# STAC_Test_Board_v1_Power.net
KiCad netlist of a schematic drawn in Altium Designer
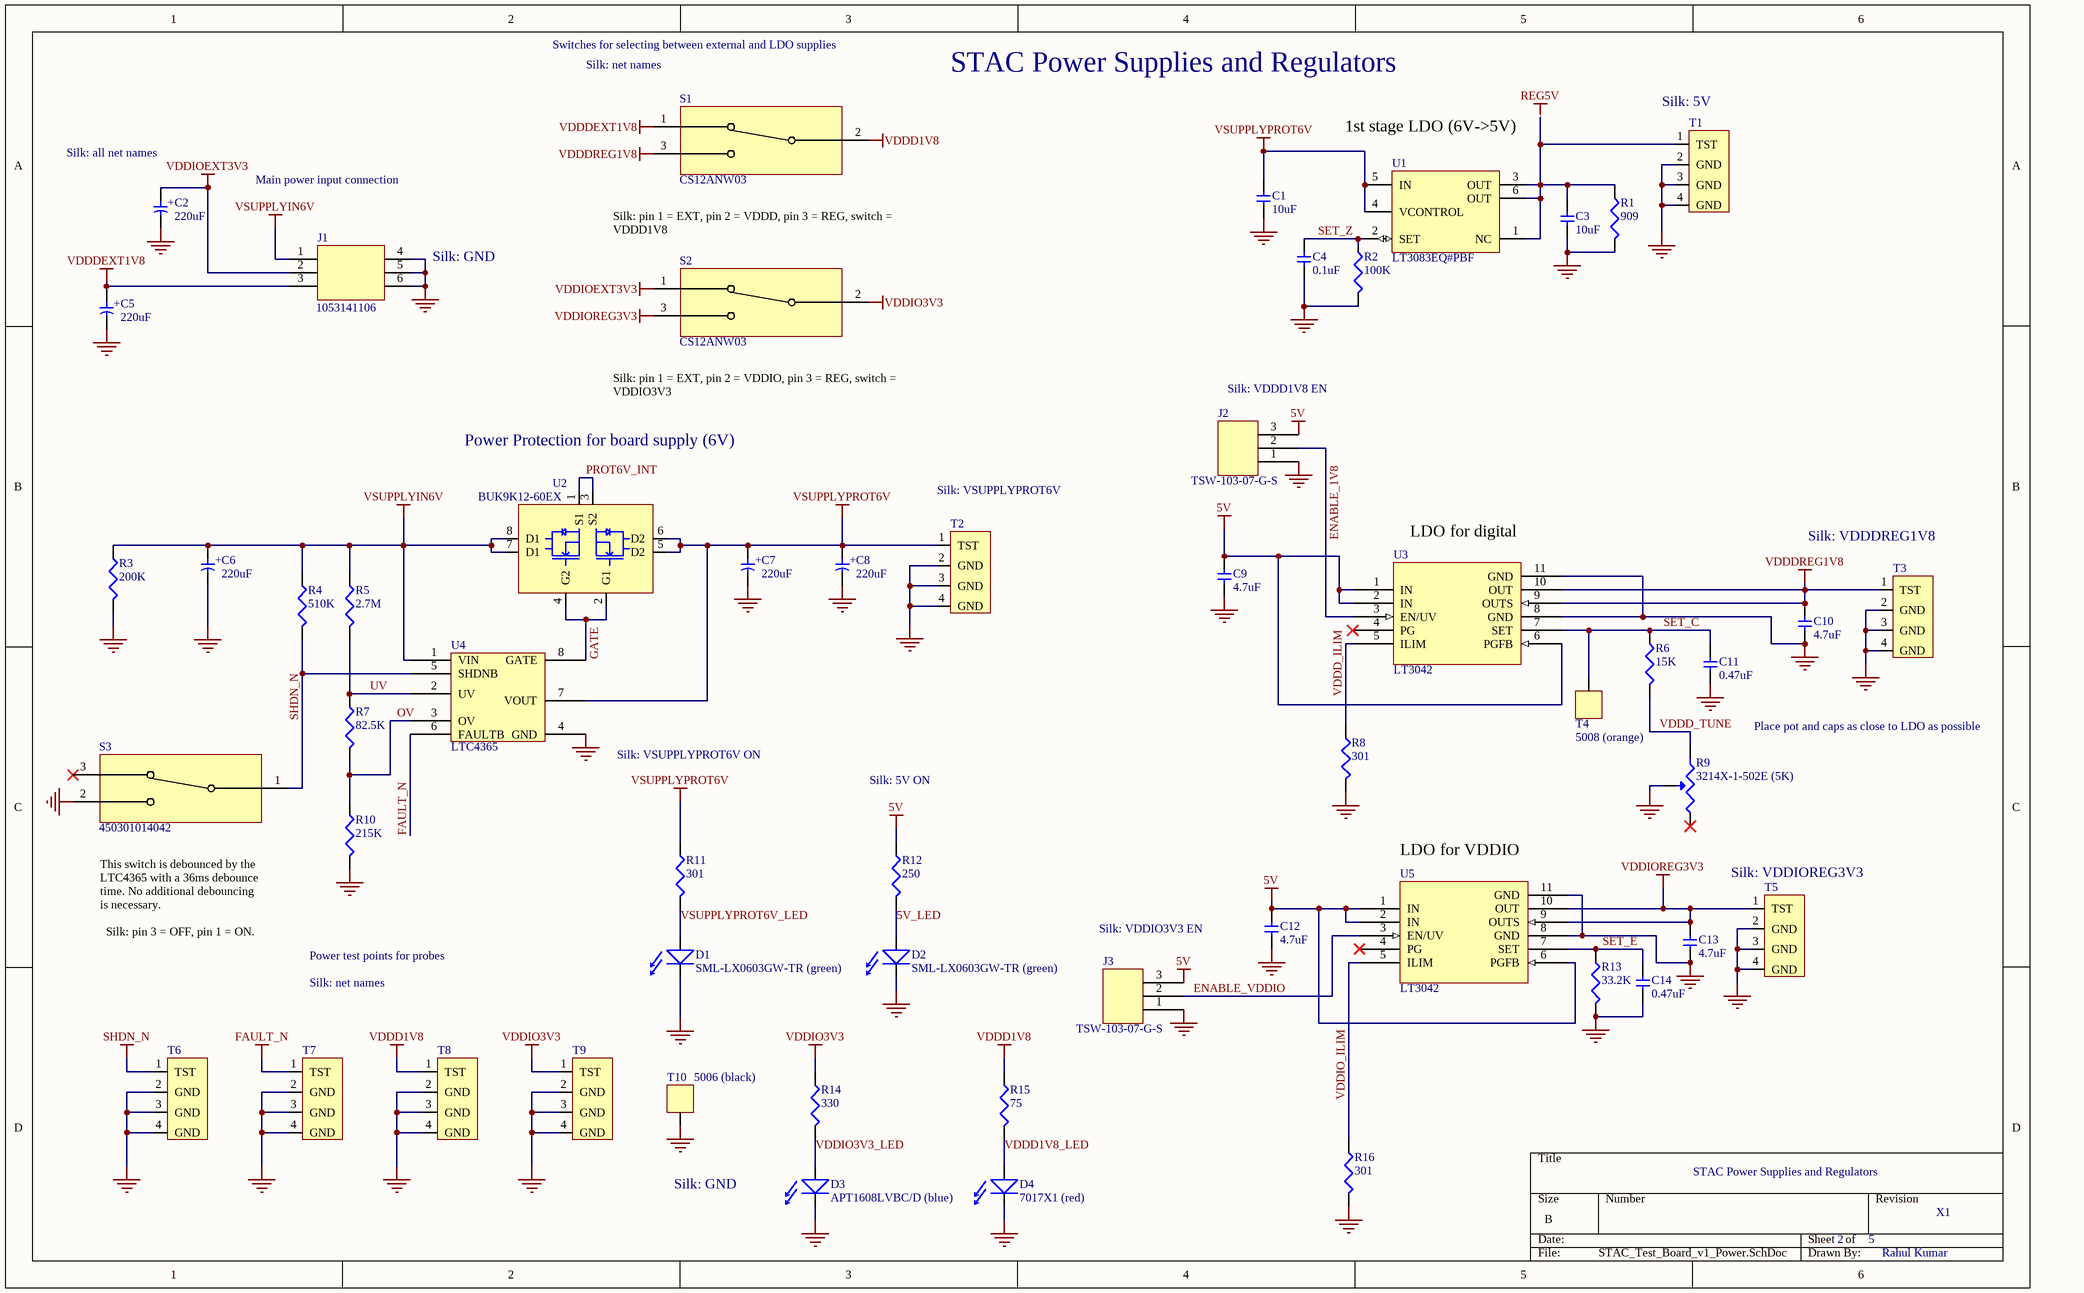
[diagram p0: STAC_Test_Board_v1_Power.SchDoc]

(export (version "E")
  (design (tool "Eeschema 10.0.6"))
  (components
    (comp (ref "C1")
      (value "10uF")
      (footprint "BWRC:0603")
      (description "Capacitor generic")
      (libsource (lib "BWRC") (part "DISCRETE_C"))
    )
    (comp (ref "C2")
      (value "220uF")
      (footprint "CAP-SMT-CAN-D")
      (description "20% 16V Alum Radial SMD")
      (libsource (lib "BWRC") (part "DISCRETE_C_POL"))
    )
    (comp (ref "C3")
      (value "10uF")
      (footprint "BWRC:0603")
      (description "Capacitor generic")
      (libsource (lib "BWRC") (part "DISCRETE_C"))
    )
    (comp (ref "C4")
      (value "0.1uF")
      (footprint "0603")
      (description "Capacitor generic")
      (libsource (lib "BWRC") (part "DISCRETE_C"))
    )
    (comp (ref "C5")
      (value "220uF")
      (footprint "CAP-SMT-CAN-D")
      (description "20% 16V Alum Radial SMD")
      (libsource (lib "BWRC") (part "DISCRETE_C_POL"))
    )
    (comp (ref "C6")
      (value "220uF")
      (footprint "CAP-SMT-CAN-D")
      (description "20% 16V Alum Radial SMD")
      (libsource (lib "BWRC") (part "DISCRETE_C_POL"))
    )
    (comp (ref "C7")
      (value "220uF")
      (footprint "CAP-SMT-CAN-D")
      (description "20% 16V Alum Radial SMD")
      (libsource (lib "BWRC") (part "DISCRETE_C_POL"))
    )
    (comp (ref "C8")
      (value "220uF")
      (footprint "CAP-SMT-CAN-D")
      (description "20% 16V Alum Radial SMD")
      (libsource (lib "BWRC") (part "DISCRETE_C_POL"))
    )
    (comp (ref "C9")
      (value "4.7uF")
      (footprint "0603")
      (description "Capacitor generic")
      (libsource (lib "BWRC") (part "DISCRETE_C"))
    )
    (comp (ref "C10")
      (value "4.7uF")
      (footprint "0603")
      (description "Capacitor generic")
      (libsource (lib "BWRC") (part "DISCRETE_C"))
    )
    (comp (ref "C11")
      (value "0.47uF")
      (footprint "0603")
      (description "Capacitor generic")
      (libsource (lib "BWRC") (part "DISCRETE_C"))
    )
    (comp (ref "C12")
      (value "4.7uF")
      (footprint "0603")
      (description "Capacitor generic")
      (libsource (lib "BWRC") (part "DISCRETE_C"))
    )
    (comp (ref "C13")
      (value "4.7uF")
      (footprint "0603")
      (description "Capacitor generic")
      (libsource (lib "BWRC") (part "DISCRETE_C"))
    )
    (comp (ref "C14")
      (value "0.47uF")
      (footprint "0603")
      (description "Capacitor generic")
      (libsource (lib "BWRC") (part "DISCRETE_C"))
    )
    (comp (ref "D1")
      (value "SML-LX0603GW-TR (green)")
      (footprint "LED-0603")
      (description "LED generic")
      (libsource (lib "BWRC") (part "DISCRETE_LED"))
    )
    (comp (ref "D2")
      (value "SML-LX0603GW-TR (green)")
      (footprint "LED-0603")
      (description "LED generic")
      (libsource (lib "BWRC") (part "DISCRETE_LED"))
    )
    (comp (ref "D3")
      (value "APT1608LVBC/D (blue)")
      (footprint "LED-0603")
      (description "LED generic")
      (libsource (lib "BWRC") (part "DISCRETE_LED"))
    )
    (comp (ref "D4")
      (value "7017X1 (red)")
      (footprint "LED-0603")
      (description "LED generic")
      (libsource (lib "BWRC") (part "DISCRETE_LED"))
    )
    (comp (ref "J1")
      (value "1053141106")
      (footprint "CON-006-2.50-8.4X12.68/2X3-RA-POST")
      (description "Con 6 pins 2x3")
      (libsource (lib "BWRC") (part "CON_006pin_2x3_alt"))
    )
    (comp (ref "J2")
      (value "TSW-103-07-G-S")
      (footprint "CON-003-100-300X100/1X3-POST")
      (description "Con 3 pins")
      (libsource (lib "BWRC") (part "CON_003pin_1x3"))
    )
    (comp (ref "J3")
      (value "TSW-103-07-G-S")
      (footprint "CON-003-100-300X100/1X3-POST")
      (description "Con 3 pins")
      (libsource (lib "BWRC") (part "CON_003pin_1x3"))
    )
    (comp (ref "R1")
      (value "909")
      (footprint "0603")
      (description "Resistor generic")
      (libsource (lib "BWRC") (part "DISCRETE_R"))
    )
    (comp (ref "R2")
      (value "100K")
      (footprint "0603")
      (description "Resistor generic")
      (libsource (lib "BWRC") (part "DISCRETE_R"))
    )
    (comp (ref "R3")
      (value "200K")
      (footprint "0603")
      (description "Resistor generic")
      (libsource (lib "BWRC") (part "DISCRETE_R"))
    )
    (comp (ref "R4")
      (value "510K")
      (footprint "0603")
      (description "Resistor generic")
      (libsource (lib "BWRC") (part "DISCRETE_R"))
    )
    (comp (ref "R5")
      (value "2.7M")
      (footprint "0603")
      (description "Resistor generic")
      (libsource (lib "BWRC") (part "DISCRETE_R"))
    )
    (comp (ref "R6")
      (value "15K")
      (footprint "0603")
      (description "Resistor generic")
      (libsource (lib "BWRC") (part "DISCRETE_R"))
    )
    (comp (ref "R7")
      (value "82.5K")
      (footprint "0603")
      (description "Resistor generic")
      (libsource (lib "BWRC") (part "DISCRETE_R"))
    )
    (comp (ref "R8")
      (value "301")
      (footprint "0603")
      (description "Resistor generic")
      (libsource (lib "BWRC") (part "DISCRETE_R"))
    )
    (comp (ref "R9")
      (value "3214X-1-502E (5K)")
      (footprint "BWRC:VR-03-100-4.8X5.7/TOP")
      (description "Potentiometer")
      (libsource (lib "BWRC") (part "DISCRETE_R_VARIABLE"))
    )
    (comp (ref "R10")
      (value "215K")
      (footprint "0603")
      (description "Resistor generic")
      (libsource (lib "BWRC") (part "DISCRETE_R"))
    )
    (comp (ref "R11")
      (value "301")
      (footprint "0603")
      (description "Resistor generic")
      (libsource (lib "BWRC") (part "DISCRETE_R"))
    )
    (comp (ref "R12")
      (value "250")
      (footprint "0603")
      (description "Resistor generic")
      (libsource (lib "BWRC") (part "DISCRETE_R"))
    )
    (comp (ref "R13")
      (value "33.2K")
      (footprint "0603")
      (description "Resistor generic")
      (libsource (lib "BWRC") (part "DISCRETE_R"))
    )
    (comp (ref "R14")
      (value "330")
      (footprint "0603")
      (description "Resistor generic")
      (libsource (lib "BWRC") (part "DISCRETE_R"))
    )
    (comp (ref "R15")
      (value "75")
      (footprint "0603")
      (description "Resistor generic")
      (libsource (lib "BWRC") (part "DISCRETE_R"))
    )
    (comp (ref "R16")
      (value "301")
      (footprint "0603")
      (description "Resistor generic")
      (libsource (lib "BWRC") (part "DISCRETE_R"))
    )
    (comp (ref "S1")
      (value "CS12ANW03")
      (footprint "SW-003-4.7-14.0X7.0/SPDT-CS")
      (description "SWITCH SLIDE SPDT")
      (libsource (lib "BWRC") (part "SWITCH_SPDT_3pin"))
    )
    (comp (ref "S2")
      (value "CS12ANW03")
      (footprint "SW-003-4.7-14.0X7.0/SPDT-CS")
      (description "SWITCH SLIDE SPDT")
      (libsource (lib "BWRC") (part "SWITCH_SPDT_3pin"))
    )
    (comp (ref "S3")
      (value "450301014042")
      (footprint "SW-003-100-10.0X2.5/SPDT-WS-SLTV")
      (description "SWITCH SLIDE SPDT alternative symbol")
      (libsource (lib "BWRC") (part "SWITCH_SPDT_3pin_alt"))
    )
    (comp (ref "T1")
      (value "TEST_PT_4")
      (footprint "BWRC:TP-04-40/ROUND-THT")
      (description "Test point 4 pads for probing")
      (libsource (lib "BWRC") (part "TEST_PT_4"))
    )
    (comp (ref "T2")
      (value "TEST_PT_4")
      (footprint "BWRC:TP-04-40/ROUND-THT")
      (description "Test point 4 pads for probing")
      (libsource (lib "BWRC") (part "TEST_PT_4"))
    )
    (comp (ref "T3")
      (value "TEST_PT_4")
      (footprint "BWRC:TP-04-40/ROUND-THT")
      (description "Test point 4 pads for probing")
      (libsource (lib "BWRC") (part "TEST_PT_4"))
    )
    (comp (ref "T4")
      (value "5008 (orange)")
      (footprint "TP-63/ROUND-THT")
      (description "Test point 1 pin")
      (libsource (lib "BWRC") (part "TEST_PT"))
    )
    (comp (ref "T5")
      (value "TEST_PT_4")
      (footprint "BWRC:TP-04-40/ROUND-THT")
      (description "Test point 4 pads for probing")
      (libsource (lib "BWRC") (part "TEST_PT_4"))
    )
    (comp (ref "T6")
      (value "TEST_PT_4")
      (footprint "BWRC:TP-04-40/ROUND-THT")
      (description "Test point 4 pads for probing")
      (libsource (lib "BWRC") (part "TEST_PT_4"))
    )
    (comp (ref "T7")
      (value "TEST_PT_4")
      (footprint "BWRC:TP-04-40/ROUND-THT")
      (description "Test point 4 pads for probing")
      (libsource (lib "BWRC") (part "TEST_PT_4"))
    )
    (comp (ref "T8")
      (value "TEST_PT_4")
      (footprint "BWRC:TP-04-40/ROUND-THT")
      (description "Test point 4 pads for probing")
      (libsource (lib "BWRC") (part "TEST_PT_4"))
    )
    (comp (ref "T9")
      (value "TEST_PT_4")
      (footprint "BWRC:TP-04-40/ROUND-THT")
      (description "Test point 4 pads for probing")
      (libsource (lib "BWRC") (part "TEST_PT_4"))
    )
    (comp (ref "T10")
      (value "5006 (black)")
      (footprint "TP-63/ROUND-THT")
      (description "Test point 1 pin")
      (libsource (lib "") (part "TEST_PT_1"))
    )
    (comp (ref "U1")
      (value "LT3083EQ#PBF")
      (footprint "TAB-05-10.2X14.2-Q-DDPAK")
      (description "3 A Single Resistor LDO 1.2 to 23 V Vin, Adj Vout")
      (libsource (lib "BWRC") (part "IC_LT3083"))
    )
    (comp (ref "U2")
      (value "BUK9K12-60EX")
      (footprint "BWRC:LCCT-08-1.27-5.3X6.2/DUAL-FET")
      (description "Dual channel NMOS FETs")
      (libsource (lib "BWRC") (part "IC_BUK9K12-60EX"))
    )
    (comp (ref "U3")
      (value "LT3042")
      (footprint "GW-10-.5-4.9/THM")
      (description "LT3042 ultralow noise, high PSRR LDO, max current 200mA")
      (libsource (lib "BWRC") (part "IC_LT3042"))
    )
    (comp (ref "U4")
      (value "LTC4365")
      (footprint "BWRC:GW-08-.65-2.9")
      (description "LTC4365 Over/Under Voltage, Reverse Supply Protection Controller")
      (libsource (lib "BWRC") (part "IC_LTC4365"))
    )
    (comp (ref "U5")
      (value "LT3042")
      (footprint "GW-10-.5-4.9/THM")
      (description "LT3042 ultralow noise, high PSRR LDO, max current 200mA")
      (libsource (lib "BWRC") (part "IC_LT3042"))
    )
  )
  (nets
    (net (code "1") (name "/5V_LED") (class "Default")
      (node (ref "D2") (pin "2") (pinfunction "2_2") (pintype "passive"))
      (node (ref "R12") (pin "2") (pinfunction "2_2") (pintype "passive"))
    )
    (net (code "2") (name "/ENABLE_1V8") (class "Default")
      (node (ref "J2") (pin "2") (pinfunction "2_2") (pintype "passive"))
      (node (ref "U3") (pin "3") (pinfunction "EN/UV_3") (pintype "input"))
    )
    (net (code "3") (name "/ENABLE_VDDIO") (class "Default")
      (node (ref "J3") (pin "2") (pinfunction "2_2") (pintype "passive"))
      (node (ref "U5") (pin "3") (pinfunction "EN/UV_3") (pintype "input"))
    )
    (net (code "4") (name "/GATE") (class "Default")
      (node (ref "U2") (pin "2") (pinfunction "G1_2") (pintype "passive"))
      (node (ref "U2") (pin "4") (pinfunction "G2_4") (pintype "passive"))
      (node (ref "U4") (pin "8") (pinfunction "GATE_8") (pintype "passive"))
    )
    (net (code "5") (name "/OV") (class "Default")
      (node (ref "R10") (pin "1") (pinfunction "1_1") (pintype "passive"))
      (node (ref "R7") (pin "2") (pinfunction "2_2") (pintype "passive"))
      (node (ref "U4") (pin "3") (pinfunction "OV_3") (pintype "passive"))
    )
    (net (code "6") (name "/PROT6V_INT") (class "Default")
      (node (ref "U2") (pin "1") (pinfunction "S1_1") (pintype "passive"))
      (node (ref "U2") (pin "3") (pinfunction "S2_3") (pintype "passive"))
    )
    (net (code "7") (name "/SET_C") (class "Default")
      (node (ref "C11") (pin "1") (pinfunction "1_1") (pintype "passive"))
      (node (ref "R6") (pin "1") (pinfunction "1_1") (pintype "passive"))
      (node (ref "T4") (pin "1") (pinfunction "1_1") (pintype "passive"))
      (node (ref "U3") (pin "7") (pinfunction "SET_7") (pintype "passive"))
    )
    (net (code "8") (name "/SET_E") (class "Default")
      (node (ref "C14") (pin "1") (pinfunction "1_1") (pintype "passive"))
      (node (ref "R13") (pin "1") (pinfunction "1_1") (pintype "passive"))
      (node (ref "U5") (pin "7") (pinfunction "SET_7") (pintype "passive"))
    )
    (net (code "9") (name "/SET_Z") (class "Default")
      (node (ref "C4") (pin "1") (pinfunction "1_1") (pintype "passive"))
      (node (ref "R2") (pin "1") (pinfunction "1_1") (pintype "passive"))
      (node (ref "U1") (pin "2") (pinfunction "SET_2") (pintype "bidirectional"))
    )
    (net (code "10") (name "/UV") (class "Default")
      (node (ref "R5") (pin "2") (pinfunction "2_2") (pintype "passive"))
      (node (ref "R7") (pin "1") (pinfunction "1_1") (pintype "passive"))
      (node (ref "U4") (pin "2") (pinfunction "UV_2") (pintype "passive"))
    )
    (net (code "11") (name "/VDDD1V8_LED") (class "Default")
      (node (ref "D4") (pin "2") (pinfunction "2_2") (pintype "passive"))
      (node (ref "R15") (pin "2") (pinfunction "2_2") (pintype "passive"))
    )
    (net (code "12") (name "/VDDD_ILIM") (class "Default")
      (node (ref "R8") (pin "1") (pinfunction "1_1") (pintype "passive"))
      (node (ref "U3") (pin "5") (pinfunction "ILIM_5") (pintype "passive"))
    )
    (net (code "13") (name "/VDDD_TUNE") (class "Default")
      (node (ref "R6") (pin "2") (pinfunction "2_2") (pintype "passive"))
      (node (ref "R9") (pin "3") (pintype "passive"))
    )
    (net (code "14") (name "/VDDIO3V3_LED") (class "Default")
      (node (ref "D3") (pin "2") (pinfunction "2_2") (pintype "passive"))
      (node (ref "R14") (pin "2") (pinfunction "2_2") (pintype "passive"))
    )
    (net (code "15") (name "/VDDIO_ILIM") (class "Default")
      (node (ref "R16") (pin "1") (pinfunction "1_1") (pintype "passive"))
      (node (ref "U5") (pin "5") (pinfunction "ILIM_5") (pintype "passive"))
    )
    (net (code "16") (name "/VSUPPLYPROT6V_LED") (class "Default")
      (node (ref "D1") (pin "2") (pinfunction "2_2") (pintype "passive"))
      (node (ref "R11") (pin "2") (pinfunction "2_2") (pintype "passive"))
    )
    (net (code "17") (name "5V") (class "Default")
      (node (ref "C12") (pin "1") (pinfunction "1_1") (pintype "passive"))
      (node (ref "C9") (pin "1") (pinfunction "1_1") (pintype "passive"))
      (node (ref "J2") (pin "3") (pinfunction "3_3") (pintype "passive"))
      (node (ref "J3") (pin "3") (pinfunction "3_3") (pintype "passive"))
      (node (ref "R12") (pin "1") (pinfunction "1_1") (pintype "passive"))
      (node (ref "U3") (pin "1") (pinfunction "IN_1") (pintype "passive"))
      (node (ref "U3") (pin "2") (pinfunction "IN_2") (pintype "passive"))
      (node (ref "U3") (pin "6") (pinfunction "PGFB_6") (pintype "input"))
      (node (ref "U5") (pin "1") (pinfunction "IN_1") (pintype "passive"))
      (node (ref "U5") (pin "2") (pinfunction "IN_2") (pintype "passive"))
      (node (ref "U5") (pin "6") (pinfunction "PGFB_6") (pintype "input"))
    )
    (net (code "18") (name "FAULT_N") (class "Default")
      (node (ref "T7") (pin "1") (pinfunction "TST_1") (pintype "passive"))
      (node (ref "U4") (pin "6") (pinfunction "FAULTB_6") (pintype "passive"))
    )
    (net (code "19") (name "GND") (class "Default")
      (node (ref "C1") (pin "2") (pinfunction "2_2") (pintype "passive"))
      (node (ref "C10") (pin "2") (pinfunction "2_2") (pintype "passive"))
      (node (ref "C11") (pin "2") (pinfunction "2_2") (pintype "passive"))
      (node (ref "C12") (pin "2") (pinfunction "2_2") (pintype "passive"))
      (node (ref "C13") (pin "2") (pinfunction "2_2") (pintype "passive"))
      (node (ref "C14") (pin "2") (pinfunction "2_2") (pintype "passive"))
      (node (ref "C2") (pin "2") (pinfunction "2_2") (pintype "passive"))
      (node (ref "C3") (pin "2") (pinfunction "2_2") (pintype "passive"))
      (node (ref "C4") (pin "2") (pinfunction "2_2") (pintype "passive"))
      (node (ref "C5") (pin "2") (pinfunction "2_2") (pintype "passive"))
      (node (ref "C6") (pin "2") (pinfunction "2_2") (pintype "passive"))
      (node (ref "C7") (pin "2") (pinfunction "2_2") (pintype "passive"))
      (node (ref "C8") (pin "2") (pinfunction "2_2") (pintype "passive"))
      (node (ref "C9") (pin "2") (pinfunction "2_2") (pintype "passive"))
      (node (ref "D1") (pin "1") (pinfunction "1_1") (pintype "passive"))
      (node (ref "D2") (pin "1") (pinfunction "1_1") (pintype "passive"))
      (node (ref "D3") (pin "1") (pinfunction "1_1") (pintype "passive"))
      (node (ref "D4") (pin "1") (pinfunction "1_1") (pintype "passive"))
      (node (ref "J1") (pin "4") (pinfunction "4_4") (pintype "passive"))
      (node (ref "J1") (pin "5") (pinfunction "5_5") (pintype "passive"))
      (node (ref "J1") (pin "6") (pinfunction "6_6") (pintype "passive"))
      (node (ref "J2") (pin "1") (pinfunction "1_1") (pintype "passive"))
      (node (ref "J3") (pin "1") (pinfunction "1_1") (pintype "passive"))
      (node (ref "R1") (pin "2") (pinfunction "2_2") (pintype "passive"))
      (node (ref "R10") (pin "2") (pinfunction "2_2") (pintype "passive"))
      (node (ref "R13") (pin "2") (pinfunction "2_2") (pintype "passive"))
      (node (ref "R16") (pin "2") (pinfunction "2_2") (pintype "passive"))
      (node (ref "R2") (pin "2") (pinfunction "2_2") (pintype "passive"))
      (node (ref "R3") (pin "2") (pinfunction "2_2") (pintype "passive"))
      (node (ref "R8") (pin "2") (pinfunction "2_2") (pintype "passive"))
      (node (ref "R9") (pin "2") (pintype "passive"))
      (node (ref "S3") (pin "2") (pinfunction "2_2") (pintype "passive"))
      (node (ref "T1") (pin "2") (pinfunction "GND_2") (pintype "passive"))
      (node (ref "T1") (pin "3") (pinfunction "GND_3") (pintype "passive"))
      (node (ref "T1") (pin "4") (pinfunction "GND_4") (pintype "passive"))
      (node (ref "T10") (pin "1") (pinfunction "1_1") (pintype "passive"))
      (node (ref "T2") (pin "2") (pinfunction "GND_2") (pintype "passive"))
      (node (ref "T2") (pin "3") (pinfunction "GND_3") (pintype "passive"))
      (node (ref "T2") (pin "4") (pinfunction "GND_4") (pintype "passive"))
      (node (ref "T3") (pin "2") (pinfunction "GND_2") (pintype "passive"))
      (node (ref "T3") (pin "3") (pinfunction "GND_3") (pintype "passive"))
      (node (ref "T3") (pin "4") (pinfunction "GND_4") (pintype "passive"))
      (node (ref "T5") (pin "2") (pinfunction "GND_2") (pintype "passive"))
      (node (ref "T5") (pin "3") (pinfunction "GND_3") (pintype "passive"))
      (node (ref "T5") (pin "4") (pinfunction "GND_4") (pintype "passive"))
      (node (ref "T6") (pin "2") (pinfunction "GND_2") (pintype "passive"))
      (node (ref "T6") (pin "3") (pinfunction "GND_3") (pintype "passive"))
      (node (ref "T6") (pin "4") (pinfunction "GND_4") (pintype "passive"))
      (node (ref "T7") (pin "2") (pinfunction "GND_2") (pintype "passive"))
      (node (ref "T7") (pin "3") (pinfunction "GND_3") (pintype "passive"))
      (node (ref "T7") (pin "4") (pinfunction "GND_4") (pintype "passive"))
      (node (ref "T8") (pin "2") (pinfunction "GND_2") (pintype "passive"))
      (node (ref "T8") (pin "3") (pinfunction "GND_3") (pintype "passive"))
      (node (ref "T8") (pin "4") (pinfunction "GND_4") (pintype "passive"))
      (node (ref "T9") (pin "2") (pinfunction "GND_2") (pintype "passive"))
      (node (ref "T9") (pin "3") (pinfunction "GND_3") (pintype "passive"))
      (node (ref "T9") (pin "4") (pinfunction "GND_4") (pintype "passive"))
      (node (ref "U3") (pin "11") (pinfunction "GND_11") (pintype "power_in"))
      (node (ref "U3") (pin "8") (pinfunction "GND_8") (pintype "power_in"))
      (node (ref "U4") (pin "4") (pinfunction "GND_4") (pintype "passive"))
      (node (ref "U5") (pin "11") (pinfunction "GND_11") (pintype "power_in"))
      (node (ref "U5") (pin "8") (pinfunction "GND_8") (pintype "power_in"))
    )
    (net (code "20") (name "REG5V") (class "Default")
      (node (ref "C3") (pin "1") (pinfunction "1_1") (pintype "passive"))
      (node (ref "R1") (pin "1") (pinfunction "1_1") (pintype "passive"))
      (node (ref "T1") (pin "1") (pinfunction "TST_1") (pintype "passive"))
      (node (ref "U1") (pin "1") (pinfunction "NC_1") (pintype "passive"))
      (node (ref "U1") (pin "3") (pinfunction "OUT_3") (pintype "power_in"))
      (node (ref "U1") (pin "6") (pinfunction "OUT_6") (pintype "power_in"))
    )
    (net (code "21") (name "SHDN_N") (class "Default")
      (node (ref "R4") (pin "2") (pinfunction "2_2") (pintype "passive"))
      (node (ref "S3") (pin "1") (pinfunction "1_1") (pintype "passive"))
      (node (ref "T6") (pin "1") (pinfunction "TST_1") (pintype "passive"))
      (node (ref "U4") (pin "5") (pinfunction "SHDNB_5") (pintype "passive"))
    )
    (net (code "22") (name "VDDD1V8") (class "Default")
      (node (ref "R15") (pin "1") (pinfunction "1_1") (pintype "passive"))
      (node (ref "S1") (pin "2") (pinfunction "3_2") (pintype "passive"))
      (node (ref "T8") (pin "1") (pinfunction "TST_1") (pintype "passive"))
    )
    (net (code "23") (name "VDDDEXT1V8") (class "Default")
      (node (ref "C5") (pin "1") (pinfunction "1_1") (pintype "passive"))
      (node (ref "J1") (pin "3") (pinfunction "3_3") (pintype "passive"))
      (node (ref "S1") (pin "1") (pinfunction "1_1") (pintype "passive"))
    )
    (net (code "24") (name "VDDDREG1V8") (class "Default")
      (node (ref "C10") (pin "1") (pinfunction "1_1") (pintype "passive"))
      (node (ref "S1") (pin "3") (pinfunction "2_3") (pintype "passive"))
      (node (ref "T3") (pin "1") (pinfunction "TST_1") (pintype "passive"))
      (node (ref "U3") (pin "10") (pinfunction "OUT_10") (pintype "power_in"))
      (node (ref "U3") (pin "9") (pinfunction "OUTS_9") (pintype "input"))
    )
    (net (code "25") (name "VDDIO3V3") (class "Default")
      (node (ref "R14") (pin "1") (pinfunction "1_1") (pintype "passive"))
      (node (ref "S2") (pin "2") (pinfunction "3_2") (pintype "passive"))
      (node (ref "T9") (pin "1") (pinfunction "TST_1") (pintype "passive"))
    )
    (net (code "26") (name "VDDIOEXT3V3") (class "Default")
      (node (ref "C2") (pin "1") (pinfunction "1_1") (pintype "passive"))
      (node (ref "J1") (pin "2") (pinfunction "2_2") (pintype "passive"))
      (node (ref "S2") (pin "1") (pinfunction "1_1") (pintype "passive"))
    )
    (net (code "27") (name "VDDIOREG3V3") (class "Default")
      (node (ref "C13") (pin "1") (pinfunction "1_1") (pintype "passive"))
      (node (ref "S2") (pin "3") (pinfunction "2_3") (pintype "passive"))
      (node (ref "T5") (pin "1") (pinfunction "TST_1") (pintype "passive"))
      (node (ref "U5") (pin "10") (pinfunction "OUT_10") (pintype "power_in"))
      (node (ref "U5") (pin "9") (pinfunction "OUTS_9") (pintype "input"))
    )
    (net (code "28") (name "VSUPPLYIN6V") (class "Default")
      (node (ref "C6") (pin "1") (pinfunction "1_1") (pintype "passive"))
      (node (ref "J1") (pin "1") (pinfunction "1_1") (pintype "passive"))
      (node (ref "R3") (pin "1") (pinfunction "1_1") (pintype "passive"))
      (node (ref "R4") (pin "1") (pinfunction "1_1") (pintype "passive"))
      (node (ref "R5") (pin "1") (pinfunction "1_1") (pintype "passive"))
      (node (ref "U2") (pin "7") (pinfunction "D1_7") (pintype "passive"))
      (node (ref "U2") (pin "8") (pinfunction "D1_8") (pintype "passive"))
      (node (ref "U4") (pin "1") (pinfunction "VIN_1") (pintype "passive"))
    )
    (net (code "29") (name "VSUPPLYPROT6V") (class "Default")
      (node (ref "C1") (pin "1") (pinfunction "1_1") (pintype "passive"))
      (node (ref "C7") (pin "1") (pinfunction "1_1") (pintype "passive"))
      (node (ref "C8") (pin "1") (pinfunction "1_1") (pintype "passive"))
      (node (ref "R11") (pin "1") (pinfunction "1_1") (pintype "passive"))
      (node (ref "T2") (pin "1") (pinfunction "TST_1") (pintype "passive"))
      (node (ref "U1") (pin "4") (pinfunction "VCONTROL_4") (pintype "power_in"))
      (node (ref "U1") (pin "5") (pinfunction "IN_5") (pintype "power_in"))
      (node (ref "U2") (pin "5") (pinfunction "D2_5") (pintype "passive"))
      (node (ref "U2") (pin "6") (pinfunction "D2_6") (pintype "passive"))
      (node (ref "U4") (pin "7") (pinfunction "VOUT_7") (pintype "passive"))
    )
    (net (code "30") (name "unconnected-(R9-Pad1)") (class "Default")
      (node (ref "R9") (pin "1") (pintype "passive+no_connect"))
    )
    (net (code "31") (name "unconnected-(S3-Pad3)") (class "Default")
      (node (ref "S3") (pin "3") (pinfunction "3_3") (pintype "passive+no_connect"))
    )
    (net (code "32") (name "unconnected-(U3-PG-Pad4)") (class "Default")
      (node (ref "U3") (pin "4") (pinfunction "PG_4") (pintype "power_in+no_connect"))
    )
    (net (code "33") (name "unconnected-(U5-PG-Pad4)") (class "Default")
      (node (ref "U5") (pin "4") (pinfunction "PG_4") (pintype "power_in+no_connect"))
    )
  )
)
